# bluetooth_3.net
KiCad netlist of a schematic drawn in Altium Designer
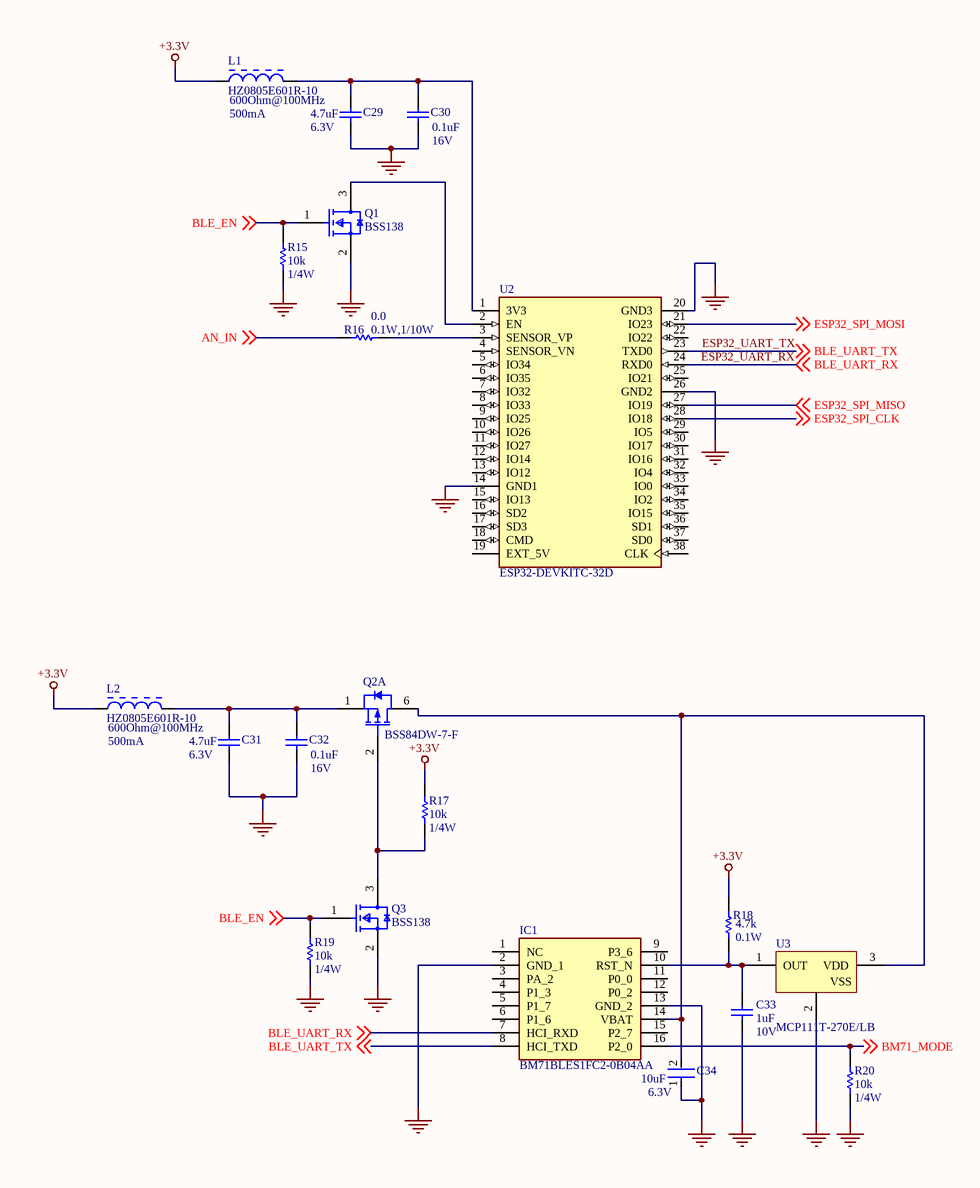
[diagram p0: bluetooth 3.SchDoc]

(export (version "E")
  (design (tool "Eeschema 10.0.6"))
  (components
    (comp (ref "C29")
      (value "4.7uF")
      (footprint "CAPC2013X145X50NL20T25")
      (fields
        (field (name "PART NUMBER") "C0805C475K9PACTU")
        (field (name "MANUFACTURER") "Kemet")
        (field (name "VOLTAGE") "6.3V")
      )
      (libsource (lib "Altium Content Vault") (part "CAP"))
    )
    (comp (ref "C30")
      (value "0.1uF")
      (footprint "CAPC1608X87X35ML15T15")
      (description "Ceramic Capacitor 0.1uF 16V +-10% X7R0603")
      (fields
        (field (name "PART NUMBER") "C0603C104M4RACTU")
        (field (name "MANUFACTURER") "Kemet")
        (field (name "VOLTAGE") "16V")
      )
      (libsource (lib "Altium Content Vault") (part "CAP"))
    )
    (comp (ref "C31")
      (value "4.7uF")
      (footprint "CAPC2013X145X50NL20T25")
      (fields
        (field (name "PART NUMBER") "C0805C475K9PACTU")
        (field (name "MANUFACTURER") "Kemet")
        (field (name "VOLTAGE") "6.3V")
      )
      (libsource (lib "Altium Content Vault") (part "CAP"))
    )
    (comp (ref "C32")
      (value "0.1uF")
      (footprint "CAPC1608X87X35ML15T15")
      (description "Ceramic Capacitor 0.1uF 16V +-10% X7R0603")
      (fields
        (field (name "PART NUMBER") "C0603C104M4RACTU")
        (field (name "MANUFACTURER") "Kemet")
        (field (name "VOLTAGE") "16V")
      )
      (libsource (lib "Altium Content Vault") (part "CAP"))
    )
    (comp (ref "C33")
      (value "1uF")
      (footprint "CAPC1608X90X35ML15T15")
      (fields
        (field (name "MANUFACTURER") "Kemet")
        (field (name "PART NUMBER") "C0603C105K8RACTU")
        (field (name "VOLTAGE") "10V")
      )
      (libsource (lib "Altium Content Vault") (part "CAP"))
    )
    (comp (ref "C34")
      (value "10uF")
      (footprint "FP-CL10-IPC_C")
      (description "Cap Ceramic 10uF 6.3V X5R ±20% Pad SMD 0603 +85°C T/R")
      (fields
        (field (name "VOLTAGE") "6.3V")
        (field (name "TOLERANCE") "20%")
        (field (name "MANUFACTURER") "Samsung")
      )
      (libsource (lib "Altium Content Vault") (part "b4654b650e69147ec39a6b967a45e02"))
    )
    (comp (ref "IC1")
      (value "BM71BLES1FC2-0B04AA")
      (footprint "SamacSys:BM71BLES1FC2_1")
      (description "Integrated Circuit")
      (fields (field (name "MOUSER PART NUMBER") "579-BM71BS1FC2-BB04"))
      (libsource (lib "SamacSys") (part "BM71BLES1FC2-0B04AA"))
    )
    (comp (ref "L1")
      (value "HZ0805E601R-10")
      (footprint "LIRD-LI0805H151R-10-2_V")
      (fields
        (field (name "IMPEDANCE @ FREQUENCY") "600Ohm@100MHz")
        (field (name "MANUFACTURER") "Laird")
        (field (name "CURRENT RATING (MAX)") "500mA")
      )
      (libsource (lib "Altium Content Vault") (part "IND-FB-2"))
    )
    (comp (ref "L2")
      (value "HZ0805E601R-10")
      (footprint "LIRD-LI0805H151R-10-2_V")
      (fields
        (field (name "IMPEDANCE @ FREQUENCY") "600Ohm@100MHz")
        (field (name "MANUFACTURER") "Laird")
        (field (name "CURRENT RATING (MAX)") "500mA")
      )
      (libsource (lib "Altium Content Vault") (part "IND-FB-2"))
    )
    (comp (ref "Q1")
      (value "BSS138")
      (footprint "FP-318-08-IPC_B")
      (description "MOSFET N-CH 50V 220MA SOT-23")
      (libsource (lib "Altium Content Vault") (part "3b9c635fedb024a5347a57b145af9cc"))
    )
    (comp (ref "Q2")
      (value "BSS84DW-7-F")
      (footprint "DIOD-SOT363-6_V")
      (description "Dual P-Channel Enhancement Mode MOSFET, 50 VDS, -55 to 150 degC, 6-Pin SOT363, RoHS, Tape and Reel")
      (fields (field (name "MANUFACTURER") "DiodesIncorporated"))
      (libsource (lib "Altium Content Vault") (part "PEMOS-SGD-SGD-6"))
    )
    (comp (ref "Q3")
      (value "BSS138")
      (footprint "FP-318-08-IPC_B")
      (description "MOSFET N-CH 50V 220MA SOT-23")
      (libsource (lib "Altium Content Vault") (part "3b9c635fedb024a5347a57b145af9cc"))
    )
    (comp (ref "R15")
      (value "10k")
      (footprint "RESC3216X70X50NL05T20")
      (description "Res Thick Film 1206 10k Ohms 5% 1/4W")
      (fields
        (field (name "PART NUMBER") "ERJ-8GEYJ103V")
        (field (name "MANUFACTURER") "Panasonic")
        (field (name "POWER") "1/4W")
      )
      (libsource (lib "Altium Content Vault") (part "RES"))
    )
    (comp (ref "R16")
      (value "0.0")
      (footprint "RESC1608X55X35LL10T10")
      (description "Chip Resistor, 0 Ohm, +/- 5%, 0.1 W, -55 to 155 degC, 0603 (1608 Metric), RoHS, Tape and Reel")
      (fields
        (field (name "POWER") "0.1W,1/10W")
        (field (name "MANUFACTURER") "Samsung-Electro-Mechanics-America,-Inc.")
        (field (name "TOLERANCE") "Jumper")
      )
      (libsource (lib "Altium Content Vault") (part "RES-2"))
    )
    (comp (ref "R17")
      (value "10k")
      (footprint "RESC3216X70X50NL05T20")
      (description "Res Thick Film 1206 10k Ohms 5% 1/4W")
      (fields
        (field (name "PART NUMBER") "ERJ-8GEYJ103V")
        (field (name "MANUFACTURER") "Panasonic")
        (field (name "POWER") "1/4W")
      )
      (libsource (lib "Altium Content Vault") (part "RES"))
    )
    (comp (ref "R18")
      (value "4.7k")
      (footprint "RESC1608X55X25LL10T15")
      (description "Chip Resistor, 4.7 KOhm, +/- 1%, 0.1 W, -55 to 155 degC, 0603 (1608 Metric), RoHS, Tape and Reel")
      (fields
        (field (name "POWER") "0.1W")
        (field (name "MANUFACTURER") "Yageo")
        (field (name "TOLERANCE") "1%")
      )
      (libsource (lib "Altium Content Vault") (part "RES-2"))
    )
    (comp (ref "R19")
      (value "10k")
      (footprint "RESC3216X70X50NL05T20")
      (description "Res Thick Film 1206 10k Ohms 5% 1/4W")
      (fields
        (field (name "PART NUMBER") "ERJ-8GEYJ103V")
        (field (name "MANUFACTURER") "Panasonic")
        (field (name "POWER") "1/4W")
      )
      (libsource (lib "Altium Content Vault") (part "RES"))
    )
    (comp (ref "R20")
      (value "10k")
      (footprint "RESC3216X70X50NL05T20")
      (description "Res Thick Film 1206 10k Ohms 5% 1/4W")
      (fields
        (field (name "PART NUMBER") "ERJ-8GEYJ103V")
        (field (name "MANUFACTURER") "Panasonic")
        (field (name "POWER") "1/4W")
      )
      (libsource (lib "Altium Content Vault") (part "RES"))
    )
    (comp (ref "U2")
      (value "ESP32-DEVKITC-32D")
      (footprint "MODULE_ESP32-DEVKITC-32D")
      (fields (field (name "MF") "Espressif Systems"))
      (libsource (lib "ESP32-DEVKITC-32D") (part "ESP32-DEVKITC-32D"))
    )
    (comp (ref "U3")
      (value "MCP111T-270E/LB")
      (footprint "SC70-LB3_N")
      (libsource (lib "Altium Content Vault") (part "PM-VLTD-MCP11X-SOT3"))
    )
  )
  (nets
    (net (code "1") (name "+3.3V") (class "Default")
      (node (ref "L1") (pin "1") (pinfunction "1_1") (pintype "passive"))
      (node (ref "L2") (pin "1") (pinfunction "1_1") (pintype "passive"))
      (node (ref "R17") (pin "1") (pinfunction "1_1") (pintype "passive"))
      (node (ref "R18") (pin "2") (pinfunction "2_2") (pintype "passive"))
    )
    (net (code "2") (name "AN_IN") (class "Default")
      (node (ref "R16") (pin "1") (pinfunction "1_1") (pintype "passive"))
    )
    (net (code "3") (name "BLE_EN") (class "Default")
      (node (ref "Q1") (pin "1") (pinfunction "G_1") (pintype "passive"))
      (node (ref "Q3") (pin "1") (pinfunction "G_1") (pintype "passive"))
      (node (ref "R15") (pin "1") (pinfunction "1_1") (pintype "passive"))
      (node (ref "R19") (pin "1") (pinfunction "1_1") (pintype "passive"))
    )
    (net (code "4") (name "BLE_UART_RX") (class "Default")
      (node (ref "IC1") (pin "7") (pinfunction "HCI_RXD_7") (pintype "passive"))
      (node (ref "U2") (pin "24") (pinfunction "RXD0_24") (pintype "input"))
    )
    (net (code "5") (name "BLE_UART_TX") (class "Default")
      (node (ref "IC1") (pin "8") (pinfunction "HCI_TXD_8") (pintype "passive"))
      (node (ref "U2") (pin "23") (pinfunction "TXD0_23") (pintype "output"))
    )
    (net (code "6") (name "BM71_MODE") (class "Default")
      (node (ref "IC1") (pin "16") (pinfunction "P2_0_16") (pintype "passive"))
      (node (ref "R20") (pin "1") (pinfunction "1_1") (pintype "passive"))
    )
    (net (code "7") (name "ESP32_SPI_CLK") (class "Default")
      (node (ref "U2") (pin "28") (pinfunction "IO18_28") (pintype "bidirectional"))
    )
    (net (code "8") (name "ESP32_SPI_MISO") (class "Default")
      (node (ref "U2") (pin "27") (pinfunction "IO19_27") (pintype "bidirectional"))
    )
    (net (code "9") (name "ESP32_SPI_MOSI") (class "Default")
      (node (ref "U2") (pin "21") (pinfunction "IO23_21") (pintype "bidirectional"))
    )
    (net (code "10") (name "GND") (class "Default")
      (node (ref "C29") (pin "1") (pinfunction "1_1") (pintype "passive"))
      (node (ref "C30") (pin "1") (pinfunction "1_1") (pintype "passive"))
      (node (ref "C31") (pin "1") (pinfunction "1_1") (pintype "passive"))
      (node (ref "C32") (pin "1") (pinfunction "1_1") (pintype "passive"))
      (node (ref "C33") (pin "1") (pinfunction "1_1") (pintype "passive"))
      (node (ref "C34") (pin "1") (pinfunction "1_1") (pintype "passive"))
      (node (ref "IC1") (pin "13") (pinfunction "GND_2_13") (pintype "passive"))
      (node (ref "IC1") (pin "2") (pinfunction "GND_1_2") (pintype "passive"))
      (node (ref "Q1") (pin "2") (pinfunction "S_2") (pintype "passive"))
      (node (ref "Q3") (pin "2") (pinfunction "S_2") (pintype "passive"))
      (node (ref "R15") (pin "2") (pinfunction "2_2") (pintype "passive"))
      (node (ref "R19") (pin "2") (pinfunction "2_2") (pintype "passive"))
      (node (ref "R20") (pin "2") (pinfunction "2_2") (pintype "passive"))
      (node (ref "U2") (pin "14") (pinfunction "GND1_14") (pintype "power_in"))
      (node (ref "U2") (pin "20") (pinfunction "GND3_20") (pintype "power_in"))
      (node (ref "U2") (pin "26") (pinfunction "GND2_26") (pintype "power_in"))
      (node (ref "U3") (pin "2") (pinfunction "VSS_2") (pintype "power_in"))
    )
    (net (code "11") (name "Net-(IC1-RST_N)") (class "Default")
      (node (ref "C33") (pin "2") (pinfunction "2_2") (pintype "passive"))
      (node (ref "IC1") (pin "10") (pinfunction "RST_N_10") (pintype "passive"))
      (node (ref "R18") (pin "1") (pinfunction "1_1") (pintype "passive"))
      (node (ref "U3") (pin "1") (pinfunction "OUT_1") (pintype "power_in"))
    )
    (net (code "12") (name "Net-(IC1-VBAT)") (class "Default")
      (node (ref "C34") (pin "2") (pinfunction "2_2") (pintype "passive"))
      (node (ref "IC1") (pin "14") (pinfunction "VBAT_14") (pintype "passive"))
      (node (ref "Q2") (pin "6") (pinfunction "D_6") (pintype "passive"))
      (node (ref "U3") (pin "3") (pinfunction "VDD_3") (pintype "power_in"))
    )
    (net (code "13") (name "Net-(Q1-D)") (class "Default")
      (node (ref "Q1") (pin "3") (pinfunction "D_3") (pintype "passive"))
      (node (ref "U2") (pin "2") (pinfunction "EN_2") (pintype "input"))
    )
    (net (code "14") (name "Net-(Q2A-G)") (class "Default")
      (node (ref "Q2") (pin "2") (pinfunction "G_2") (pintype "passive"))
      (node (ref "Q3") (pin "3") (pinfunction "D_3") (pintype "passive"))
      (node (ref "R17") (pin "2") (pinfunction "2_2") (pintype "passive"))
    )
    (net (code "15") (name "Net-(Q2A-S)") (class "Default")
      (node (ref "C31") (pin "2") (pinfunction "2_2") (pintype "passive"))
      (node (ref "C32") (pin "2") (pinfunction "2_2") (pintype "passive"))
      (node (ref "L2") (pin "2") (pinfunction "2_2") (pintype "passive"))
      (node (ref "Q2") (pin "1") (pinfunction "S_1") (pintype "passive"))
    )
    (net (code "16") (name "Net-(U2-3V3)") (class "Default")
      (node (ref "C29") (pin "2") (pinfunction "2_2") (pintype "passive"))
      (node (ref "C30") (pin "2") (pinfunction "2_2") (pintype "passive"))
      (node (ref "L1") (pin "2") (pinfunction "2_2") (pintype "passive"))
      (node (ref "U2") (pin "1") (pinfunction "3V3_1") (pintype "power_in"))
    )
    (net (code "17") (name "Net-(U2-SENSOR_VP)") (class "Default")
      (node (ref "R16") (pin "2") (pinfunction "2_2") (pintype "passive"))
      (node (ref "U2") (pin "3") (pinfunction "SENSOR_VP_3") (pintype "input"))
    )
    (net (code "18") (name "unconnected-(IC1-NC-Pad1)") (class "Default")
      (node (ref "IC1") (pin "1") (pinfunction "NC_1") (pintype "passive"))
    )
    (net (code "19") (name "unconnected-(IC1-P0_0-Pad11)") (class "Default")
      (node (ref "IC1") (pin "11") (pinfunction "P0_0_11") (pintype "passive"))
    )
    (net (code "20") (name "unconnected-(IC1-P0_2-Pad12)") (class "Default")
      (node (ref "IC1") (pin "12") (pinfunction "P0_2_12") (pintype "passive"))
    )
    (net (code "21") (name "unconnected-(IC1-P1_3-Pad4)") (class "Default")
      (node (ref "IC1") (pin "4") (pinfunction "P1_3_4") (pintype "passive"))
    )
    (net (code "22") (name "unconnected-(IC1-P1_6-Pad6)") (class "Default")
      (node (ref "IC1") (pin "6") (pinfunction "P1_6_6") (pintype "passive"))
    )
    (net (code "23") (name "unconnected-(IC1-P1_7-Pad5)") (class "Default")
      (node (ref "IC1") (pin "5") (pinfunction "P1_7_5") (pintype "passive"))
    )
    (net (code "24") (name "unconnected-(IC1-P2_7-Pad15)") (class "Default")
      (node (ref "IC1") (pin "15") (pinfunction "P2_7_15") (pintype "passive"))
    )
    (net (code "25") (name "unconnected-(IC1-P3_6-Pad9)") (class "Default")
      (node (ref "IC1") (pin "9") (pinfunction "P3_6_9") (pintype "passive"))
    )
    (net (code "26") (name "unconnected-(IC1-PA_2-Pad3)") (class "Default")
      (node (ref "IC1") (pin "3") (pinfunction "PA_2_3") (pintype "passive"))
    )
    (net (code "27") (name "unconnected-(U2-CLK-Pad38)") (class "Default")
      (node (ref "U2") (pin "38") (pinfunction "CLK_38") (pintype "input"))
    )
    (net (code "28") (name "unconnected-(U2-CMD-Pad18)") (class "Default")
      (node (ref "U2") (pin "18") (pinfunction "CMD_18") (pintype "bidirectional"))
    )
    (net (code "29") (name "unconnected-(U2-EXT_5V-Pad19)") (class "Default")
      (node (ref "U2") (pin "19") (pinfunction "EXT_5V_19") (pintype "power_in"))
    )
    (net (code "30") (name "unconnected-(U2-IO0-Pad33)") (class "Default")
      (node (ref "U2") (pin "33") (pinfunction "IO0_33") (pintype "bidirectional"))
    )
    (net (code "31") (name "unconnected-(U2-IO2-Pad34)") (class "Default")
      (node (ref "U2") (pin "34") (pinfunction "IO2_34") (pintype "bidirectional"))
    )
    (net (code "32") (name "unconnected-(U2-IO4-Pad32)") (class "Default")
      (node (ref "U2") (pin "32") (pinfunction "IO4_32") (pintype "bidirectional"))
    )
    (net (code "33") (name "unconnected-(U2-IO5-Pad29)") (class "Default")
      (node (ref "U2") (pin "29") (pinfunction "IO5_29") (pintype "bidirectional"))
    )
    (net (code "34") (name "unconnected-(U2-IO12-Pad13)") (class "Default")
      (node (ref "U2") (pin "13") (pinfunction "IO12_13") (pintype "bidirectional"))
    )
    (net (code "35") (name "unconnected-(U2-IO13-Pad15)") (class "Default")
      (node (ref "U2") (pin "15") (pinfunction "IO13_15") (pintype "bidirectional"))
    )
    (net (code "36") (name "unconnected-(U2-IO14-Pad12)") (class "Default")
      (node (ref "U2") (pin "12") (pinfunction "IO14_12") (pintype "bidirectional"))
    )
    (net (code "37") (name "unconnected-(U2-IO15-Pad35)") (class "Default")
      (node (ref "U2") (pin "35") (pinfunction "IO15_35") (pintype "bidirectional"))
    )
    (net (code "38") (name "unconnected-(U2-IO16-Pad31)") (class "Default")
      (node (ref "U2") (pin "31") (pinfunction "IO16_31") (pintype "bidirectional"))
    )
    (net (code "39") (name "unconnected-(U2-IO17-Pad30)") (class "Default")
      (node (ref "U2") (pin "30") (pinfunction "IO17_30") (pintype "bidirectional"))
    )
    (net (code "40") (name "unconnected-(U2-IO21-Pad25)") (class "Default")
      (node (ref "U2") (pin "25") (pinfunction "IO21_25") (pintype "bidirectional"))
    )
    (net (code "41") (name "unconnected-(U2-IO22-Pad22)") (class "Default")
      (node (ref "U2") (pin "22") (pinfunction "IO22_22") (pintype "bidirectional"))
    )
    (net (code "42") (name "unconnected-(U2-IO25-Pad9)") (class "Default")
      (node (ref "U2") (pin "9") (pinfunction "IO25_9") (pintype "bidirectional"))
    )
    (net (code "43") (name "unconnected-(U2-IO26-Pad10)") (class "Default")
      (node (ref "U2") (pin "10") (pinfunction "IO26_10") (pintype "bidirectional"))
    )
    (net (code "44") (name "unconnected-(U2-IO27-Pad11)") (class "Default")
      (node (ref "U2") (pin "11") (pinfunction "IO27_11") (pintype "bidirectional"))
    )
    (net (code "45") (name "unconnected-(U2-IO32-Pad7)") (class "Default")
      (node (ref "U2") (pin "7") (pinfunction "IO32_7") (pintype "bidirectional"))
    )
    (net (code "46") (name "unconnected-(U2-IO33-Pad8)") (class "Default")
      (node (ref "U2") (pin "8") (pinfunction "IO33_8") (pintype "bidirectional"))
    )
    (net (code "47") (name "unconnected-(U2-IO34-Pad5)") (class "Default")
      (node (ref "U2") (pin "5") (pinfunction "IO34_5") (pintype "bidirectional"))
    )
    (net (code "48") (name "unconnected-(U2-IO35-Pad6)") (class "Default")
      (node (ref "U2") (pin "6") (pinfunction "IO35_6") (pintype "bidirectional"))
    )
    (net (code "49") (name "unconnected-(U2-SD0-Pad37)") (class "Default")
      (node (ref "U2") (pin "37") (pinfunction "SD0_37") (pintype "bidirectional"))
    )
    (net (code "50") (name "unconnected-(U2-SD1-Pad36)") (class "Default")
      (node (ref "U2") (pin "36") (pinfunction "SD1_36") (pintype "bidirectional"))
    )
    (net (code "51") (name "unconnected-(U2-SD2-Pad16)") (class "Default")
      (node (ref "U2") (pin "16") (pinfunction "SD2_16") (pintype "bidirectional"))
    )
    (net (code "52") (name "unconnected-(U2-SD3-Pad17)") (class "Default")
      (node (ref "U2") (pin "17") (pinfunction "SD3_17") (pintype "bidirectional"))
    )
    (net (code "53") (name "unconnected-(U2-SENSOR_VN-Pad4)") (class "Default")
      (node (ref "U2") (pin "4") (pinfunction "SENSOR_VN_4") (pintype "input"))
    )
  )
)
